# shield.net
KiCad netlist of a schematic drawn in EAGLE
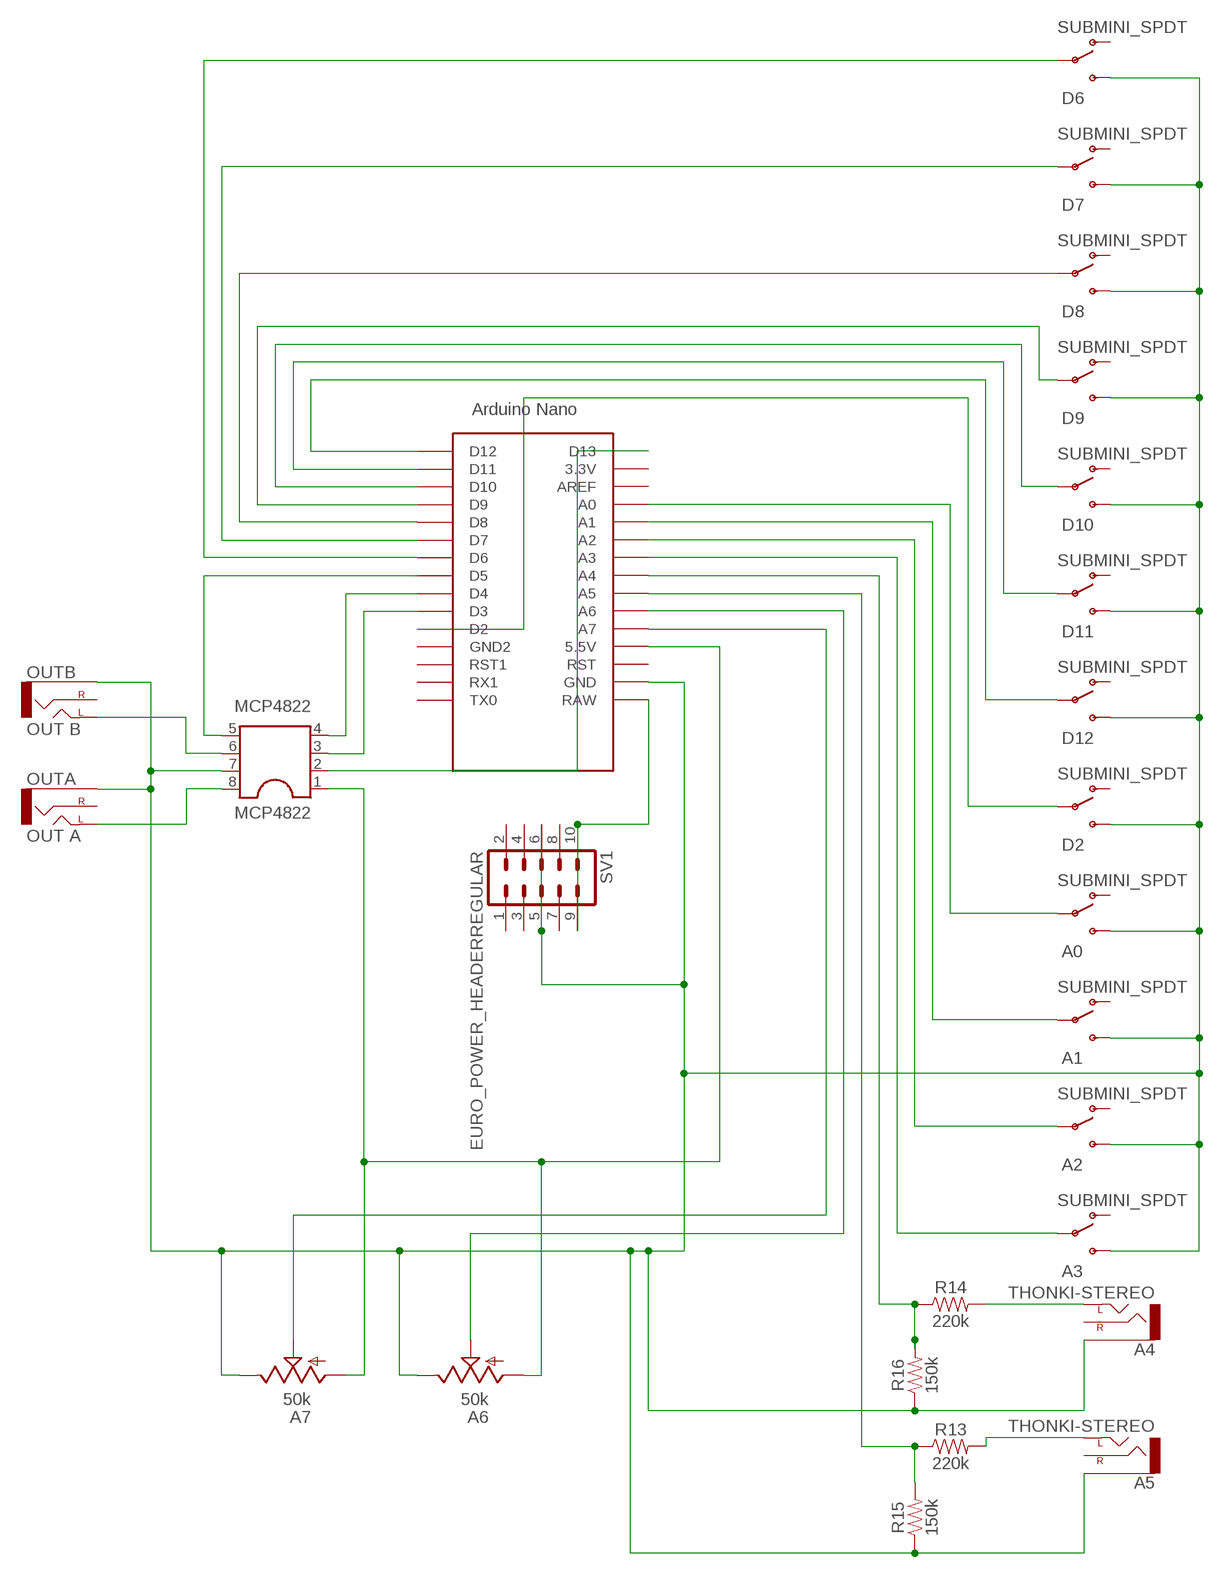
[diagram p0: schematic, sheet 1]

(export (version "E")
  (design (tool "Eeschema 10.0.6"))
  (components
    (comp (ref "A0")
      (value "SUBMINI_SPDT")
      (footprint "eagle-import:SUBMINI_TOGGLE")
      (libsource (lib "eagle-import") (part "SUBMINI_SPDT"))
    )
    (comp (ref "A1")
      (value "SUBMINI_SPDT")
      (footprint "eagle-import:SUBMINI_TOGGLE")
      (libsource (lib "eagle-import") (part "SUBMINI_SPDT"))
    )
    (comp (ref "A2")
      (value "SUBMINI_SPDT")
      (footprint "eagle-import:SUBMINI_TOGGLE")
      (libsource (lib "eagle-import") (part "SUBMINI_SPDT"))
    )
    (comp (ref "A3")
      (value "SUBMINI_SPDT")
      (footprint "eagle-import:SUBMINI_TOGGLE")
      (libsource (lib "eagle-import") (part "SUBMINI_SPDT"))
    )
    (comp (ref "A4")
      (value "THONKI-STEREO")
      (footprint "eagle-import:WQP-PJ366ST_JACK")
      (libsource (lib "eagle-import") (part "THONKI-STEREO"))
    )
    (comp (ref "A5")
      (value "THONKI-STEREO")
      (footprint "eagle-import:WQP-PJ366ST_JACK")
      (libsource (lib "eagle-import") (part "THONKI-STEREO"))
    )
    (comp (ref "A6")
      (value "50k")
      (footprint "eagle-import:9MM_SNAP-IN_POT")
      (libsource (lib "eagle-import") (part "9MM_SNAP-IN_POT_"))
    )
    (comp (ref "A7")
      (value "50k")
      (footprint "eagle-import:9MM_SNAP-IN_POT")
      (libsource (lib "eagle-import") (part "9MM_SNAP-IN_POT_"))
    )
    (comp (ref "D2")
      (value "SUBMINI_SPDT")
      (footprint "eagle-import:SUBMINI_TOGGLE")
      (libsource (lib "eagle-import") (part "SUBMINI_SPDT"))
    )
    (comp (ref "D6")
      (value "SUBMINI_SPDT")
      (footprint "eagle-import:SUBMINI_TOGGLE")
      (libsource (lib "eagle-import") (part "SUBMINI_SPDT"))
    )
    (comp (ref "D7")
      (value "SUBMINI_SPDT")
      (footprint "eagle-import:SUBMINI_TOGGLE")
      (libsource (lib "eagle-import") (part "SUBMINI_SPDT"))
    )
    (comp (ref "D8")
      (value "SUBMINI_SPDT")
      (footprint "eagle-import:SUBMINI_TOGGLE")
      (libsource (lib "eagle-import") (part "SUBMINI_SPDT"))
    )
    (comp (ref "D9")
      (value "SUBMINI_SPDT")
      (footprint "eagle-import:SUBMINI_TOGGLE")
      (libsource (lib "eagle-import") (part "SUBMINI_SPDT"))
    )
    (comp (ref "D10")
      (value "SUBMINI_SPDT")
      (footprint "eagle-import:SUBMINI_TOGGLE")
      (libsource (lib "eagle-import") (part "SUBMINI_SPDT"))
    )
    (comp (ref "D11")
      (value "SUBMINI_SPDT")
      (footprint "eagle-import:SUBMINI_TOGGLE")
      (libsource (lib "eagle-import") (part "SUBMINI_SPDT"))
    )
    (comp (ref "D12")
      (value "SUBMINI_SPDT")
      (footprint "eagle-import:SUBMINI_TOGGLE")
      (libsource (lib "eagle-import") (part "SUBMINI_SPDT"))
    )
    (comp (ref "MCP4822")
      (value "MCP4822")
      (footprint "eagle-import:DIL08")
      (libsource (lib "eagle-import") (part "DIL8"))
    )
    (comp (ref "OUTA")
      (value "OUT A")
      (footprint "eagle-import:WQP-PJ366ST_JACK")
      (libsource (lib "eagle-import") (part "THONKI-STEREO"))
    )
    (comp (ref "OUTB")
      (value "OUT B")
      (footprint "eagle-import:WQP-PJ366ST_JACK")
      (libsource (lib "eagle-import") (part "THONKI-STEREO"))
    )
    (comp (ref "R13")
      (value "220k")
      (footprint "eagle-import:AXIAL-0.3")
      (libsource (lib "eagle-import") (part "10KOHM-HORIZ-1/4W-5%"))
    )
    (comp (ref "R14")
      (value "220k")
      (footprint "eagle-import:AXIAL-0.3")
      (libsource (lib "eagle-import") (part "10KOHM-HORIZ-1/4W-5%"))
    )
    (comp (ref "R15")
      (value "150k")
      (footprint "eagle-import:AXIAL-0.3")
      (libsource (lib "eagle-import") (part "10KOHM-HORIZ-1/4W-5%"))
    )
    (comp (ref "R16")
      (value "150k")
      (footprint "eagle-import:AXIAL-0.3")
      (libsource (lib "eagle-import") (part "10KOHM-HORIZ-1/4W-5%"))
    )
    (comp (ref "SV1")
      (value "EURO_POWER_HEADERREGULAR")
      (footprint "eagle-import:EURO_POWER_HEADER")
      (libsource (lib "eagle-import") (part "EURO_POWER_HEADERREGULAR"))
    )
    (comp (ref "U$1")
      (value "NANO")
      (footprint "eagle-import:NANO")
      (libsource (lib "eagle-import") (part "NANO"))
    )
  )
  (nets
    (net (code "1") (name "Net-(A0-COMMON)") (class "Default")
      (node (ref "A0") (pin "COM") (pinfunction "COMMON_COM") (pintype "passive"))
      (node (ref "U$1") (pin "A0") (pinfunction "A0_A0") (pintype "bidirectional"))
    )
    (net (code "2") (name "Net-(A0-S)") (class "Default")
      (node (ref "A0") (pin "3") (pinfunction "S_3") (pintype "passive"))
      (node (ref "A1") (pin "3") (pinfunction "S_3") (pintype "passive"))
      (node (ref "A2") (pin "3") (pinfunction "S_3") (pintype "passive"))
      (node (ref "A3") (pin "3") (pinfunction "S_3") (pintype "passive"))
      (node (ref "A4") (pin "P$3_SLEEVE") (pinfunction "SLEEVE_P$3_SLEEVE") (pintype "bidirectional"))
      (node (ref "A5") (pin "P$3_SLEEVE") (pinfunction "SLEEVE_P$3_SLEEVE") (pintype "bidirectional"))
      (node (ref "A6") (pin "3") (pinfunction "E_3") (pintype "passive"))
      (node (ref "A7") (pin "3") (pinfunction "E_3") (pintype "passive"))
      (node (ref "D10") (pin "3") (pinfunction "S_3") (pintype "passive"))
      (node (ref "D11") (pin "3") (pinfunction "S_3") (pintype "passive"))
      (node (ref "D12") (pin "3") (pinfunction "S_3") (pintype "passive"))
      (node (ref "D2") (pin "3") (pinfunction "S_3") (pintype "passive"))
      (node (ref "D6") (pin "3") (pinfunction "S_3") (pintype "passive"))
      (node (ref "D7") (pin "3") (pinfunction "S_3") (pintype "passive"))
      (node (ref "D8") (pin "3") (pinfunction "S_3") (pintype "passive"))
      (node (ref "D9") (pin "3") (pinfunction "S_3") (pintype "passive"))
      (node (ref "MCP4822") (pin "7") (pinfunction "7_7") (pintype "passive"))
      (node (ref "OUTA") (pin "P$3_SLEEVE") (pinfunction "SLEEVE_P$3_SLEEVE") (pintype "bidirectional"))
      (node (ref "OUTB") (pin "P$3_SLEEVE") (pinfunction "SLEEVE_P$3_SLEEVE") (pintype "bidirectional"))
      (node (ref "R15") (pin "P$1") (pinfunction "1_P$1") (pintype "passive"))
      (node (ref "R16") (pin "P$1") (pinfunction "1_P$1") (pintype "passive"))
      (node (ref "SV1") (pin "5") (pinfunction "5_5") (pintype "passive"))
      (node (ref "SV1") (pin "6") (pinfunction "6_6") (pintype "passive"))
      (node (ref "U$1") (pin "GND") (pinfunction "GND_GND") (pintype "bidirectional"))
    )
    (net (code "3") (name "Net-(A1-COMMON)") (class "Default")
      (node (ref "A1") (pin "COM") (pinfunction "COMMON_COM") (pintype "passive"))
      (node (ref "U$1") (pin "A1") (pinfunction "A1_A1") (pintype "bidirectional"))
    )
    (net (code "4") (name "Net-(A2-COMMON)") (class "Default")
      (node (ref "A2") (pin "COM") (pinfunction "COMMON_COM") (pintype "passive"))
      (node (ref "U$1") (pin "A2") (pinfunction "A2_A2") (pintype "bidirectional"))
    )
    (net (code "5") (name "Net-(A3-COMMON)") (class "Default")
      (node (ref "A3") (pin "COM") (pinfunction "COMMON_COM") (pintype "passive"))
      (node (ref "U$1") (pin "A3") (pinfunction "A3_A3") (pintype "bidirectional"))
    )
    (net (code "6") (name "Net-(A4-LEFT)") (class "Default")
      (node (ref "A4") (pin "P$1_TIP") (pinfunction "LEFT_P$1_TIP") (pintype "bidirectional"))
      (node (ref "R14") (pin "P$2") (pinfunction "2_P$2") (pintype "passive"))
    )
    (net (code "7") (name "Net-(A5-LEFT)") (class "Default")
      (node (ref "A5") (pin "P$1_TIP") (pinfunction "LEFT_P$1_TIP") (pintype "bidirectional"))
      (node (ref "R13") (pin "P$2") (pinfunction "2_P$2") (pintype "passive"))
    )
    (net (code "8") (name "Net-(A6-A)") (class "Default")
      (node (ref "A6") (pin "1") (pinfunction "A_1") (pintype "passive"))
      (node (ref "A7") (pin "1") (pinfunction "A_1") (pintype "passive"))
      (node (ref "MCP4822") (pin "1") (pinfunction "1_1") (pintype "passive"))
      (node (ref "U$1") (pin "5V") (pinfunction "5.5V_5V") (pintype "bidirectional"))
    )
    (net (code "9") (name "Net-(A6-S)") (class "Default")
      (node (ref "A6") (pin "2") (pinfunction "S_2") (pintype "passive"))
      (node (ref "U$1") (pin "A6") (pinfunction "A6_A6") (pintype "bidirectional"))
    )
    (net (code "10") (name "Net-(A7-S)") (class "Default")
      (node (ref "A7") (pin "2") (pinfunction "S_2") (pintype "passive"))
      (node (ref "U$1") (pin "A7") (pinfunction "A7_A7") (pintype "bidirectional"))
    )
    (net (code "11") (name "Net-(D2-COMMON)") (class "Default")
      (node (ref "D2") (pin "COM") (pinfunction "COMMON_COM") (pintype "passive"))
      (node (ref "U$1") (pin "D2") (pinfunction "D2_D2") (pintype "bidirectional"))
    )
    (net (code "12") (name "Net-(D6-COMMON)") (class "Default")
      (node (ref "D6") (pin "COM") (pinfunction "COMMON_COM") (pintype "passive"))
      (node (ref "U$1") (pin "D6") (pinfunction "D6_D6") (pintype "bidirectional"))
    )
    (net (code "13") (name "Net-(D7-COMMON)") (class "Default")
      (node (ref "D7") (pin "COM") (pinfunction "COMMON_COM") (pintype "passive"))
      (node (ref "U$1") (pin "D7") (pinfunction "D7_D7") (pintype "bidirectional"))
    )
    (net (code "14") (name "Net-(D8-COMMON)") (class "Default")
      (node (ref "D8") (pin "COM") (pinfunction "COMMON_COM") (pintype "passive"))
      (node (ref "U$1") (pin "D8") (pinfunction "D8_D8") (pintype "bidirectional"))
    )
    (net (code "15") (name "Net-(D9-COMMON)") (class "Default")
      (node (ref "D9") (pin "COM") (pinfunction "COMMON_COM") (pintype "passive"))
      (node (ref "U$1") (pin "D9") (pinfunction "D9_D9") (pintype "bidirectional"))
    )
    (net (code "16") (name "Net-(D10-COMMON)") (class "Default")
      (node (ref "D10") (pin "COM") (pinfunction "COMMON_COM") (pintype "passive"))
      (node (ref "U$1") (pin "D10") (pinfunction "D10_D10") (pintype "bidirectional"))
    )
    (net (code "17") (name "Net-(D11-COMMON)") (class "Default")
      (node (ref "D11") (pin "COM") (pinfunction "COMMON_COM") (pintype "passive"))
      (node (ref "U$1") (pin "D11") (pinfunction "D11_D11") (pintype "bidirectional"))
    )
    (net (code "18") (name "Net-(D12-COMMON)") (class "Default")
      (node (ref "D12") (pin "COM") (pinfunction "COMMON_COM") (pintype "passive"))
      (node (ref "U$1") (pin "D12") (pinfunction "D12_D12") (pintype "bidirectional"))
    )
    (net (code "19") (name "Net-(MCP4822-Pad2)") (class "Default")
      (node (ref "MCP4822") (pin "2") (pinfunction "2_2") (pintype "passive"))
      (node (ref "U$1") (pin "D13") (pinfunction "D13_D13") (pintype "bidirectional"))
    )
    (net (code "20") (name "Net-(MCP4822-Pad3)") (class "Default")
      (node (ref "MCP4822") (pin "3") (pinfunction "3_3") (pintype "passive"))
      (node (ref "U$1") (pin "D3") (pinfunction "D3_D3") (pintype "bidirectional"))
    )
    (net (code "21") (name "Net-(MCP4822-Pad4)") (class "Default")
      (node (ref "MCP4822") (pin "4") (pinfunction "4_4") (pintype "passive"))
      (node (ref "U$1") (pin "D4") (pinfunction "D4_D4") (pintype "bidirectional"))
    )
    (net (code "22") (name "Net-(MCP4822-Pad5)") (class "Default")
      (node (ref "MCP4822") (pin "5") (pinfunction "5_5") (pintype "passive"))
      (node (ref "U$1") (pin "D5") (pinfunction "D5_D5") (pintype "bidirectional"))
    )
    (net (code "23") (name "Net-(OUTA-LEFT)") (class "Default")
      (node (ref "MCP4822") (pin "8") (pinfunction "8_8") (pintype "passive"))
      (node (ref "OUTA") (pin "P$1_TIP") (pinfunction "LEFT_P$1_TIP") (pintype "bidirectional"))
    )
    (net (code "24") (name "Net-(OUTB-LEFT)") (class "Default")
      (node (ref "MCP4822") (pin "6") (pinfunction "6_6") (pintype "passive"))
      (node (ref "OUTB") (pin "P$1_TIP") (pinfunction "LEFT_P$1_TIP") (pintype "bidirectional"))
    )
    (net (code "25") (name "Net-(R13-1)") (class "Default")
      (node (ref "R13") (pin "P$1") (pinfunction "1_P$1") (pintype "passive"))
      (node (ref "R15") (pin "P$2") (pinfunction "2_P$2") (pintype "passive"))
      (node (ref "U$1") (pin "A5") (pinfunction "A5_A5") (pintype "bidirectional"))
    )
    (net (code "26") (name "Net-(R14-1)") (class "Default")
      (node (ref "R14") (pin "P$1") (pinfunction "1_P$1") (pintype "passive"))
      (node (ref "R16") (pin "P$2") (pinfunction "2_P$2") (pintype "passive"))
      (node (ref "U$1") (pin "A4") (pinfunction "A4_A4") (pintype "bidirectional"))
    )
    (net (code "27") (name "Net-(SV1-Pad10)") (class "Default")
      (node (ref "SV1") (pin "10") (pinfunction "10_10") (pintype "passive"))
      (node (ref "SV1") (pin "9") (pinfunction "9_9") (pintype "passive"))
      (node (ref "U$1") (pin "RAW") (pinfunction "RAW_RAW") (pintype "bidirectional"))
    )
    (net (code "28") (name "unconnected-(A0-O-Pad1)") (class "Default")
      (node (ref "A0") (pin "1") (pinfunction "O_1") (pintype "passive"))
    )
    (net (code "29") (name "unconnected-(A1-O-Pad1)") (class "Default")
      (node (ref "A1") (pin "1") (pinfunction "O_1") (pintype "passive"))
    )
    (net (code "30") (name "unconnected-(A2-O-Pad1)") (class "Default")
      (node (ref "A2") (pin "1") (pinfunction "O_1") (pintype "passive"))
    )
    (net (code "31") (name "unconnected-(A3-O-Pad1)") (class "Default")
      (node (ref "A3") (pin "1") (pinfunction "O_1") (pintype "passive"))
    )
    (net (code "32") (name "unconnected-(A4-RIGHT-PadP$2_SWITCH)") (class "Default")
      (node (ref "A4") (pin "P$2_SWITCH") (pinfunction "RIGHT_P$2_SWITCH") (pintype "bidirectional"))
    )
    (net (code "33") (name "unconnected-(A5-RIGHT-PadP$2_SWITCH)") (class "Default")
      (node (ref "A5") (pin "P$2_SWITCH") (pinfunction "RIGHT_P$2_SWITCH") (pintype "bidirectional"))
    )
    (net (code "34") (name "unconnected-(D2-O-Pad1)") (class "Default")
      (node (ref "D2") (pin "1") (pinfunction "O_1") (pintype "passive"))
    )
    (net (code "35") (name "unconnected-(D6-O-Pad1)") (class "Default")
      (node (ref "D6") (pin "1") (pinfunction "O_1") (pintype "passive"))
    )
    (net (code "36") (name "unconnected-(D7-O-Pad1)") (class "Default")
      (node (ref "D7") (pin "1") (pinfunction "O_1") (pintype "passive"))
    )
    (net (code "37") (name "unconnected-(D8-O-Pad1)") (class "Default")
      (node (ref "D8") (pin "1") (pinfunction "O_1") (pintype "passive"))
    )
    (net (code "38") (name "unconnected-(D9-O-Pad1)") (class "Default")
      (node (ref "D9") (pin "1") (pinfunction "O_1") (pintype "passive"))
    )
    (net (code "39") (name "unconnected-(D10-O-Pad1)") (class "Default")
      (node (ref "D10") (pin "1") (pinfunction "O_1") (pintype "passive"))
    )
    (net (code "40") (name "unconnected-(D11-O-Pad1)") (class "Default")
      (node (ref "D11") (pin "1") (pinfunction "O_1") (pintype "passive"))
    )
    (net (code "41") (name "unconnected-(D12-O-Pad1)") (class "Default")
      (node (ref "D12") (pin "1") (pinfunction "O_1") (pintype "passive"))
    )
    (net (code "42") (name "unconnected-(OUTA-RIGHT-PadP$2_SWITCH)") (class "Default")
      (node (ref "OUTA") (pin "P$2_SWITCH") (pinfunction "RIGHT_P$2_SWITCH") (pintype "bidirectional"))
    )
    (net (code "43") (name "unconnected-(OUTB-RIGHT-PadP$2_SWITCH)") (class "Default")
      (node (ref "OUTB") (pin "P$2_SWITCH") (pinfunction "RIGHT_P$2_SWITCH") (pintype "bidirectional"))
    )
    (net (code "44") (name "unconnected-(SV1-Pad1)") (class "Default")
      (node (ref "SV1") (pin "1") (pinfunction "1_1") (pintype "passive"))
    )
    (net (code "45") (name "unconnected-(SV1-Pad2)") (class "Default")
      (node (ref "SV1") (pin "2") (pinfunction "2_2") (pintype "passive"))
    )
    (net (code "46") (name "unconnected-(SV1-Pad3)") (class "Default")
      (node (ref "SV1") (pin "3") (pinfunction "3_3") (pintype "passive"))
    )
    (net (code "47") (name "unconnected-(SV1-Pad4)") (class "Default")
      (node (ref "SV1") (pin "4") (pinfunction "4_4") (pintype "passive"))
    )
    (net (code "48") (name "unconnected-(SV1-Pad7)") (class "Default")
      (node (ref "SV1") (pin "7") (pinfunction "7_7") (pintype "passive"))
    )
    (net (code "49") (name "unconnected-(SV1-Pad8)") (class "Default")
      (node (ref "SV1") (pin "8") (pinfunction "8_8") (pintype "passive"))
    )
    (net (code "50") (name "unconnected-(U$1-GND2-PadGND1)") (class "Default")
      (node (ref "U$1") (pin "GND1") (pinfunction "GND2_GND1") (pintype "bidirectional"))
    )
    (net (code "51") (name "unconnected-(U$1-Pad3.3V)") (class "Default")
      (node (ref "U$1") (pin "3.3V") (pinfunction "3.3V_3.3V") (pintype "bidirectional"))
    )
    (net (code "52") (name "unconnected-(U$1-PadAREF)") (class "Default")
      (node (ref "U$1") (pin "AREF") (pinfunction "AREF_AREF") (pintype "bidirectional"))
    )
    (net (code "53") (name "unconnected-(U$1-PadICSP1)") (class "Default")
      (node (ref "U$1") (pin "ICSP1") (pinfunction "ICSP1_ICSP1") (pintype "bidirectional"))
    )
    (net (code "54") (name "unconnected-(U$1-PadICSP2)") (class "Default")
      (node (ref "U$1") (pin "ICSP2") (pinfunction "ICSP2_ICSP2") (pintype "bidirectional"))
    )
    (net (code "55") (name "unconnected-(U$1-PadICSP3)") (class "Default")
      (node (ref "U$1") (pin "ICSP3") (pinfunction "ICSP3_ICSP3") (pintype "bidirectional"))
    )
    (net (code "56") (name "unconnected-(U$1-PadICSP4)") (class "Default")
      (node (ref "U$1") (pin "ICSP4") (pinfunction "ICSP4_ICSP4") (pintype "bidirectional"))
    )
    (net (code "57") (name "unconnected-(U$1-PadICSP5)") (class "Default")
      (node (ref "U$1") (pin "ICSP5") (pinfunction "ICSP5_ICSP5") (pintype "bidirectional"))
    )
    (net (code "58") (name "unconnected-(U$1-PadICSP6)") (class "Default")
      (node (ref "U$1") (pin "ICSP6") (pinfunction "ICSP6_ICSP6") (pintype "bidirectional"))
    )
    (net (code "59") (name "unconnected-(U$1-PadRST)") (class "Default")
      (node (ref "U$1") (pin "RST") (pinfunction "RST_RST") (pintype "bidirectional"))
    )
    (net (code "60") (name "unconnected-(U$1-PadRST1)") (class "Default")
      (node (ref "U$1") (pin "RST1") (pinfunction "RST1_RST1") (pintype "bidirectional"))
    )
    (net (code "61") (name "unconnected-(U$1-PadRX1)") (class "Default")
      (node (ref "U$1") (pin "RX1") (pinfunction "RX1_RX1") (pintype "bidirectional"))
    )
    (net (code "62") (name "unconnected-(U$1-PadTX0)") (class "Default")
      (node (ref "U$1") (pin "TX0") (pinfunction "TX0_TX0") (pintype "bidirectional"))
    )
  )
)
